# DCmotor.net
KiCad netlist of a schematic drawn in Altium Designer
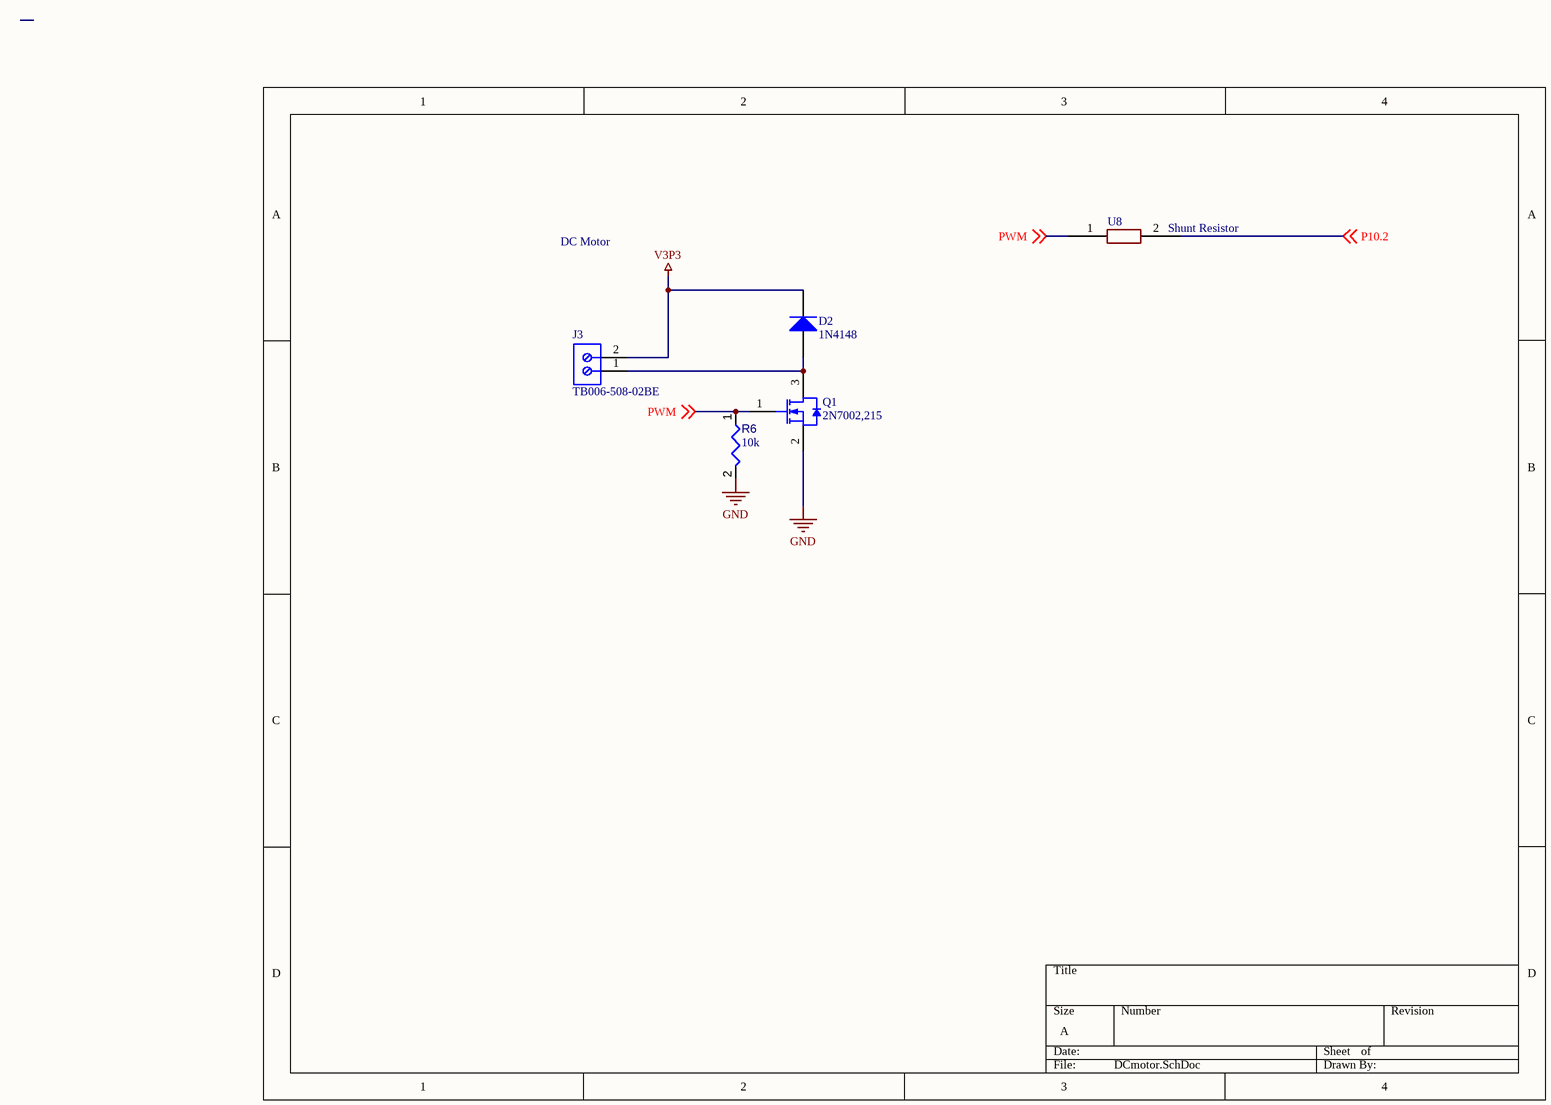
[diagram p0: DCmotor.SchDoc]

(export (version "E")
  (design (tool "Eeschema 10.0.6"))
  (components
    (comp (ref "D2")
      (value "1N4148")
      (footprint "NXP-SOD27-2_V")
      (description "High Speed Diode, 100 V, 0.45 A, -65 to 175 degC, 2-Pin SOD27, RoHS, Bulk")
      (fields (field (name "POWER") "500mW") (field (name "MANUFACTURER") "Fairchild"))
      (libsource (lib "Daksh Sharma") (part "D-AK-2"))
    )
    (comp (ref "J3")
      (value "CONN_TB006_-508-02BE")
      (footprint "CUI_TB006 -508-02BE")
      (description "2~24 Poles, Screw Type, Horizontal, 5.08 Pitch, 26~14 (AWG), Terminal Block Connector")
      (fields
        (field (name "MF") "CUI Devices")
        (field (name "MP") "TB006 -508-02BE")
        (field (name "MANUFACTURER PART NUMBER") "TB006-508-02BE")
      )
      (libsource (lib "ECE453_S24") (part "CONN_TB006_-508-02BE"))
    )
    (comp (ref "Q1")
      (value "2N7002,215")
      (footprint "NXP-SOT23-3_V")
      (fields (field (name "POWER") "830mW") (field (name "MANUFACTURER") "NXP Semiconductors"))
      (libsource (lib "Daksh Sharma") (part "NEMOS-GSD-3"))
    )
    (comp (ref "R6")
      (value "10k")
      (footprint "RESC2013X50X35ML15T15")
      (description "Chip Resistor, 10 KOhm, +/- 1%, 125 mW, -55 to 155 degC, 0805 (2012 Metric)")
      (fields (field (name "TOLERANCE") "1%") (field (name "POWER") "125mW"))
      (libsource (lib "Daksh Sharma") (part "RES-2"))
    )
    (comp (ref "U8")
      (value "Shunt Resistor")
      (footprint "SHUNT")
      (description "Fixed Resistor, Metal Glaze/thick Film, 0.125W, 0ohm, Surface Mount, 0805")
      (fields (field (name "POWER") "125mW"))
      (libsource (lib "uw-madison-parts") (part "Shunt"))
    )
  )
  (nets
    (net (code "1") (name "GND") (class "Default")
      (node (ref "Q1") (pin "2") (pinfunction "S_2") (pintype "passive"))
      (node (ref "R6") (pin "2") (pinfunction "2_2") (pintype "passive"))
    )
    (net (code "2") (name "Net-(D2-A)") (class "Default")
      (node (ref "D2") (pin "1") (pinfunction "A_1") (pintype "passive"))
      (node (ref "J3") (pin "1") (pinfunction "1_1") (pintype "passive"))
      (node (ref "Q1") (pin "3") (pinfunction "D_3") (pintype "passive"))
    )
    (net (code "3") (name "P10.2") (class "Default")
      (node (ref "U8") (pin "2") (pinfunction "2_2") (pintype "passive"))
    )
    (net (code "4") (name "PWM") (class "Default")
      (node (ref "Q1") (pin "1") (pinfunction "G_1") (pintype "passive"))
      (node (ref "R6") (pin "1") (pinfunction "1_1") (pintype "passive"))
      (node (ref "U8") (pin "1") (pinfunction "1_1") (pintype "passive"))
    )
    (net (code "5") (name "V3P3") (class "Default")
      (node (ref "D2") (pin "2") (pinfunction "K_2") (pintype "passive"))
      (node (ref "J3") (pin "2") (pinfunction "2_2") (pintype "passive"))
    )
  )
)
